# GimbalMotorController2017.net
KiCad netlist of a schematic drawn in EAGLE
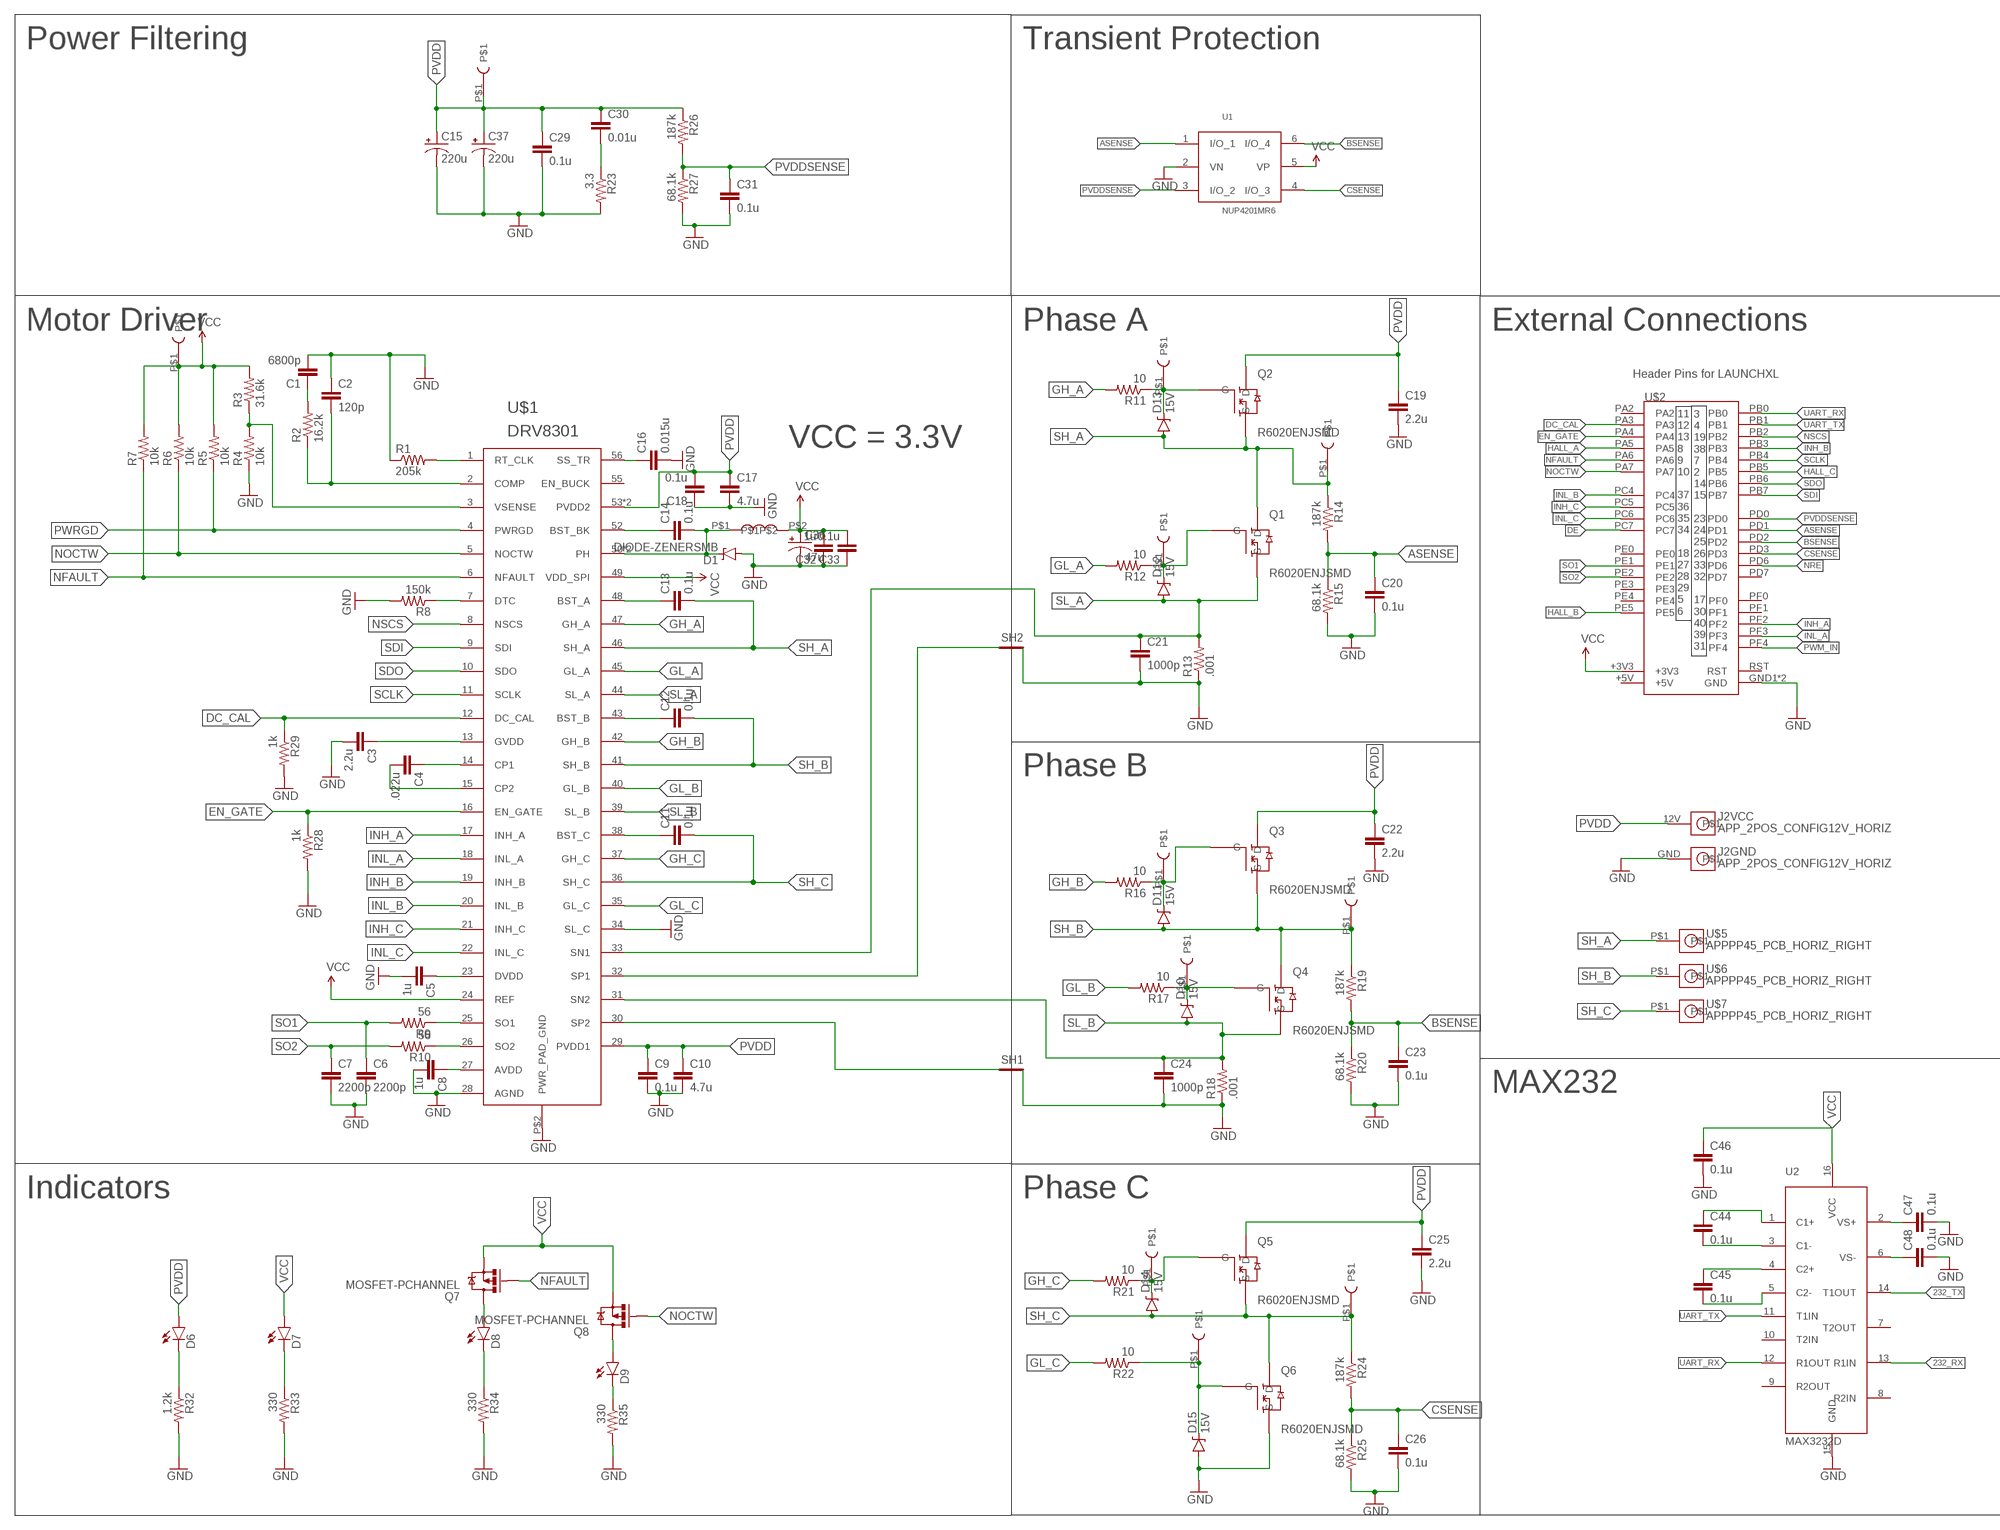
[diagram p0: schematic, sheet 1, part 1 of 2]
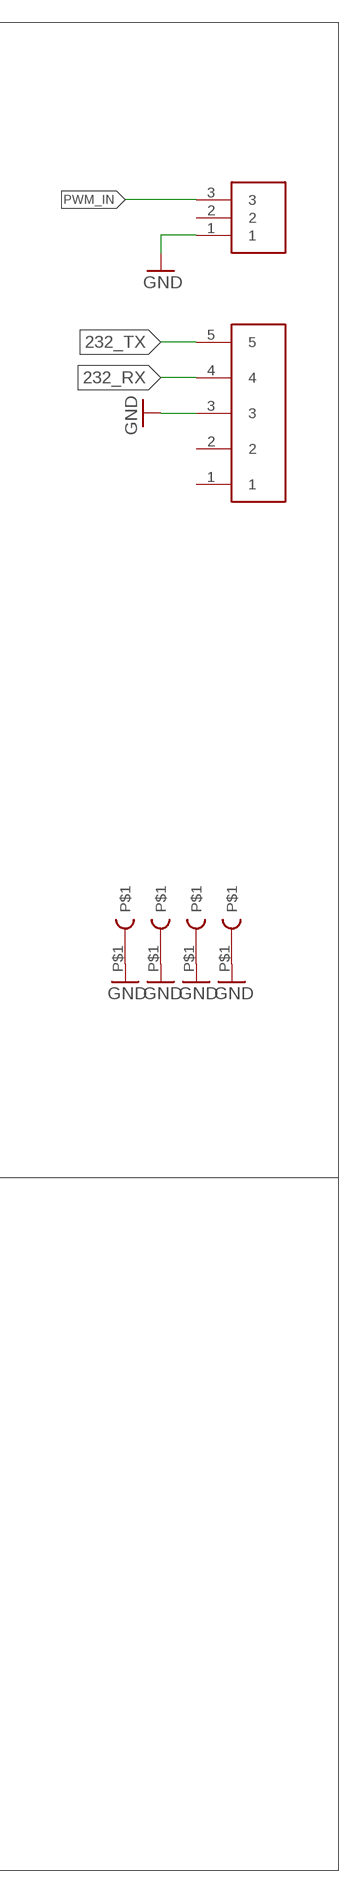
[diagram p1: schematic, sheet 1, part 2 of 2]

(export (version "E")
  (design (tool "Eeschema 10.0.6"))
  (components
    (comp (ref "C1")
      (value "6800p")
      (footprint "eagle-import:0805")
      (libsource (lib "eagle-import") (part "CAP0805"))
    )
    (comp (ref "C2")
      (value "120p")
      (footprint "eagle-import:0805")
      (libsource (lib "eagle-import") (part "CAP0805"))
    )
    (comp (ref "C3")
      (value "2.2u")
      (footprint "eagle-import:1206")
      (libsource (lib "eagle-import") (part "CAP1206"))
    )
    (comp (ref "C4")
      (value ".022u")
      (footprint "eagle-import:0805")
      (libsource (lib "eagle-import") (part "CAP0805"))
    )
    (comp (ref "C5")
      (value "1u")
      (footprint "eagle-import:0805")
      (libsource (lib "eagle-import") (part "CAP0805"))
    )
    (comp (ref "C6")
      (value "2200p")
      (footprint "eagle-import:0805")
      (libsource (lib "eagle-import") (part "CAP0805"))
    )
    (comp (ref "C7")
      (value "2200p")
      (footprint "eagle-import:0805")
      (libsource (lib "eagle-import") (part "CAP0805"))
    )
    (comp (ref "C8")
      (value "1u")
      (footprint "eagle-import:0805")
      (libsource (lib "eagle-import") (part "CAP0805"))
    )
    (comp (ref "C9")
      (value "0.1u")
      (footprint "eagle-import:0805")
      (libsource (lib "eagle-import") (part "CAP0805"))
    )
    (comp (ref "C10")
      (value "4.7u")
      (footprint "eagle-import:1206")
      (libsource (lib "eagle-import") (part "CAP1206"))
    )
    (comp (ref "C11")
      (value "0.1u")
      (footprint "eagle-import:0805")
      (libsource (lib "eagle-import") (part "CAP0805"))
    )
    (comp (ref "C12")
      (value "0.1u")
      (footprint "eagle-import:0805")
      (libsource (lib "eagle-import") (part "CAP0805"))
    )
    (comp (ref "C13")
      (value "0.1u")
      (footprint "eagle-import:0805")
      (libsource (lib "eagle-import") (part "CAP0805"))
    )
    (comp (ref "C14")
      (value "0.1u")
      (footprint "eagle-import:0805")
      (libsource (lib "eagle-import") (part "CAP0805"))
    )
    (comp (ref "C15")
      (value "220u")
      (footprint "eagle-import:CPOL-RADIAL-1000UF-25V")
      (libsource (lib "eagle-import") (part "CAP_POLPTH4"))
    )
    (comp (ref "C16")
      (value "0.015u")
      (footprint "eagle-import:0805")
      (libsource (lib "eagle-import") (part "CAP0805"))
    )
    (comp (ref "C17")
      (value "4.7u")
      (footprint "eagle-import:1206")
      (libsource (lib "eagle-import") (part "CAP1206"))
    )
    (comp (ref "C18")
      (value "0.1u")
      (footprint "eagle-import:0805")
      (libsource (lib "eagle-import") (part "CAP0805"))
    )
    (comp (ref "C19")
      (value "2.2u")
      (footprint "eagle-import:1206")
      (libsource (lib "eagle-import") (part "CAP1206"))
    )
    (comp (ref "C20")
      (value "0.1u")
      (footprint "eagle-import:0805")
      (libsource (lib "eagle-import") (part "CAP0805"))
    )
    (comp (ref "C21")
      (value "1000p")
      (footprint "eagle-import:0805")
      (libsource (lib "eagle-import") (part "CAP0805"))
    )
    (comp (ref "C22")
      (value "2.2u")
      (footprint "eagle-import:1206")
      (libsource (lib "eagle-import") (part "CAP1206"))
    )
    (comp (ref "C23")
      (value "0.1u")
      (footprint "eagle-import:0805")
      (libsource (lib "eagle-import") (part "CAP0805"))
    )
    (comp (ref "C24")
      (value "1000p")
      (footprint "eagle-import:0805")
      (libsource (lib "eagle-import") (part "CAP0805"))
    )
    (comp (ref "C25")
      (value "2.2u")
      (footprint "eagle-import:1206")
      (libsource (lib "eagle-import") (part "CAP1206"))
    )
    (comp (ref "C26")
      (value "0.1u")
      (footprint "eagle-import:0805")
      (libsource (lib "eagle-import") (part "CAP0805"))
    )
    (comp (ref "C29")
      (value "0.1u")
      (footprint "eagle-import:0805")
      (libsource (lib "eagle-import") (part "CAP0805"))
    )
    (comp (ref "C30")
      (value "0.01u")
      (footprint "eagle-import:0805")
      (libsource (lib "eagle-import") (part "CAP0805"))
    )
    (comp (ref "C31")
      (value "0.1u")
      (footprint "eagle-import:0805")
      (libsource (lib "eagle-import") (part "CAP0805"))
    )
    (comp (ref "C32")
      (value "1u")
      (footprint "eagle-import:0805")
      (libsource (lib "eagle-import") (part "CAP0805"))
    )
    (comp (ref "C33")
      (value "0.1u")
      (footprint "eagle-import:0805")
      (libsource (lib "eagle-import") (part "CAP0805"))
    )
    (comp (ref "C36")
      (value "47u")
      (footprint "eagle-import:CPOL-RADIAL-100UF-25V")
      (libsource (lib "eagle-import") (part "CAP_POLPTH1"))
    )
    (comp (ref "C37")
      (value "220u")
      (footprint "eagle-import:CPOL-RADIAL-1000UF-25V")
      (libsource (lib "eagle-import") (part "CAP_POLPTH4"))
    )
    (comp (ref "C44")
      (value "0.1u")
      (footprint "eagle-import:0805")
      (libsource (lib "eagle-import") (part "CAP0805"))
    )
    (comp (ref "C45")
      (value "0.1u")
      (footprint "eagle-import:0805")
      (libsource (lib "eagle-import") (part "CAP0805"))
    )
    (comp (ref "C46")
      (value "0.1u")
      (footprint "eagle-import:0805")
      (libsource (lib "eagle-import") (part "CAP0805"))
    )
    (comp (ref "C47")
      (value "0.1u")
      (footprint "eagle-import:0805")
      (libsource (lib "eagle-import") (part "CAP0805"))
    )
    (comp (ref "C48")
      (value "0.1u")
      (footprint "eagle-import:0805")
      (libsource (lib "eagle-import") (part "CAP0805"))
    )
    (comp (ref "D1")
      (value "DIODE-ZENERSMB")
      (footprint "eagle-import:SMB-DIODE")
      (libsource (lib "eagle-import") (part "DIODE-ZENERSMB"))
    )
    (comp (ref "D6")
      (value "LED1206")
      (footprint "eagle-import:LED-1206")
      (libsource (lib "eagle-import") (part "LED1206"))
    )
    (comp (ref "D7")
      (value "LED1206")
      (footprint "eagle-import:LED-1206")
      (libsource (lib "eagle-import") (part "LED1206"))
    )
    (comp (ref "D8")
      (value "LED1206")
      (footprint "eagle-import:LED-1206")
      (libsource (lib "eagle-import") (part "LED1206"))
    )
    (comp (ref "D9")
      (value "LED1206")
      (footprint "eagle-import:LED-1206")
      (libsource (lib "eagle-import") (part "LED1206"))
    )
    (comp (ref "D10")
      (value "15V")
      (footprint "eagle-import:SOD-323")
      (libsource (lib "eagle-import") (part "DIODE-ZENER3.3V"))
    )
    (comp (ref "D11")
      (value "15V")
      (footprint "eagle-import:SOD-323")
      (libsource (lib "eagle-import") (part "DIODE-ZENER3.3V"))
    )
    (comp (ref "D12")
      (value "15V")
      (footprint "eagle-import:SOD-323")
      (libsource (lib "eagle-import") (part "DIODE-ZENER3.3V"))
    )
    (comp (ref "D13")
      (value "15V")
      (footprint "eagle-import:SOD-323")
      (libsource (lib "eagle-import") (part "DIODE-ZENER3.3V"))
    )
    (comp (ref "D14")
      (value "15V")
      (footprint "eagle-import:SOD-323")
      (libsource (lib "eagle-import") (part "DIODE-ZENER3.3V"))
    )
    (comp (ref "D15")
      (value "15V")
      (footprint "eagle-import:SOD-323")
      (libsource (lib "eagle-import") (part "DIODE-ZENER3.3V"))
    )
    (comp (ref "J1")
      (value "SL03THROUGH_HOLE")
      (footprint "eagle-import:MOLEX_SL_03_TH")
      (fields (field (name "PARTNO") "0705550002"))
      (libsource (lib "eagle-import") (part "SL03THROUGH_HOLE"))
    )
    (comp (ref "J2")
      (value "APP_2POS_CONFIG12V_HORIZ")
      (footprint "eagle-import:APP45_12V_HORIZ_CONFIG")
      (libsource (lib "eagle-import") (part "APP_2POS_CONFIG12V_HORIZ"))
    )
    (comp (ref "Q1")
      (value "R6020ENJSMD")
      (footprint "eagle-import:D2PACK")
      (libsource (lib "eagle-import") (part "R6020ENJSMD"))
    )
    (comp (ref "Q2")
      (value "R6020ENJSMD")
      (footprint "eagle-import:D2PACK")
      (libsource (lib "eagle-import") (part "R6020ENJSMD"))
    )
    (comp (ref "Q3")
      (value "R6020ENJSMD")
      (footprint "eagle-import:D2PACK")
      (libsource (lib "eagle-import") (part "R6020ENJSMD"))
    )
    (comp (ref "Q4")
      (value "R6020ENJSMD")
      (footprint "eagle-import:D2PACK")
      (libsource (lib "eagle-import") (part "R6020ENJSMD"))
    )
    (comp (ref "Q5")
      (value "R6020ENJSMD")
      (footprint "eagle-import:D2PACK")
      (libsource (lib "eagle-import") (part "R6020ENJSMD"))
    )
    (comp (ref "Q6")
      (value "R6020ENJSMD")
      (footprint "eagle-import:D2PACK")
      (libsource (lib "eagle-import") (part "R6020ENJSMD"))
    )
    (comp (ref "Q7")
      (value "MOSFET-PCHANNEL")
      (footprint "eagle-import:SOT23-3")
      (libsource (lib "eagle-import") (part "MOSFET-PCHANNEL"))
    )
    (comp (ref "Q8")
      (value "MOSFET-PCHANNEL")
      (footprint "eagle-import:SOT23-3")
      (libsource (lib "eagle-import") (part "MOSFET-PCHANNEL"))
    )
    (comp (ref "R1")
      (value "205k")
      (footprint "eagle-import:0805")
      (libsource (lib "eagle-import") (part "RESISTOR0805-RES"))
    )
    (comp (ref "R2")
      (value "16.2k")
      (footprint "eagle-import:0805")
      (libsource (lib "eagle-import") (part "RESISTOR0805-RES"))
    )
    (comp (ref "R3")
      (value "31.6k")
      (footprint "eagle-import:0805")
      (libsource (lib "eagle-import") (part "RESISTOR0805-RES"))
    )
    (comp (ref "R4")
      (value "10k")
      (footprint "eagle-import:0805")
      (libsource (lib "eagle-import") (part "RESISTOR0805-RES"))
    )
    (comp (ref "R5")
      (value "10k")
      (footprint "eagle-import:0805")
      (libsource (lib "eagle-import") (part "RESISTOR0805-RES"))
    )
    (comp (ref "R6")
      (value "10k")
      (footprint "eagle-import:0805")
      (libsource (lib "eagle-import") (part "RESISTOR0805-RES"))
    )
    (comp (ref "R7")
      (value "10k")
      (footprint "eagle-import:0805")
      (libsource (lib "eagle-import") (part "RESISTOR0805-RES"))
    )
    (comp (ref "R8")
      (value "150k")
      (footprint "eagle-import:0805")
      (libsource (lib "eagle-import") (part "RESISTOR0805-RES"))
    )
    (comp (ref "R9")
      (value "56")
      (footprint "eagle-import:0805")
      (libsource (lib "eagle-import") (part "RESISTOR0805-RES"))
    )
    (comp (ref "R10")
      (value "56")
      (footprint "eagle-import:0805")
      (libsource (lib "eagle-import") (part "RESISTOR0805-RES"))
    )
    (comp (ref "R11")
      (value "10")
      (footprint "eagle-import:0805")
      (libsource (lib "eagle-import") (part "RESISTOR0805-RES"))
    )
    (comp (ref "R12")
      (value "10")
      (footprint "eagle-import:0805")
      (libsource (lib "eagle-import") (part "RESISTOR0805-RES"))
    )
    (comp (ref "R13")
      (value ".001")
      (footprint "eagle-import:1206")
      (libsource (lib "eagle-import") (part "RESISTOR1206"))
    )
    (comp (ref "R14")
      (value "187k")
      (footprint "eagle-import:0805")
      (libsource (lib "eagle-import") (part "RESISTOR0805-RES"))
    )
    (comp (ref "R15")
      (value "68.1k")
      (footprint "eagle-import:0805")
      (libsource (lib "eagle-import") (part "RESISTOR0805-RES"))
    )
    (comp (ref "R16")
      (value "10")
      (footprint "eagle-import:0805")
      (libsource (lib "eagle-import") (part "RESISTOR0805-RES"))
    )
    (comp (ref "R17")
      (value "10")
      (footprint "eagle-import:0805")
      (libsource (lib "eagle-import") (part "RESISTOR0805-RES"))
    )
    (comp (ref "R18")
      (value ".001")
      (footprint "eagle-import:1206")
      (libsource (lib "eagle-import") (part "RESISTOR1206"))
    )
    (comp (ref "R19")
      (value "187k")
      (footprint "eagle-import:0805")
      (libsource (lib "eagle-import") (part "RESISTOR0805-RES"))
    )
    (comp (ref "R20")
      (value "68.1k")
      (footprint "eagle-import:0805")
      (libsource (lib "eagle-import") (part "RESISTOR0805-RES"))
    )
    (comp (ref "R21")
      (value "10")
      (footprint "eagle-import:0805")
      (libsource (lib "eagle-import") (part "RESISTOR0805-RES"))
    )
    (comp (ref "R22")
      (value "10")
      (footprint "eagle-import:0805")
      (libsource (lib "eagle-import") (part "RESISTOR0805-RES"))
    )
    (comp (ref "R23")
      (value "3.3")
      (footprint "eagle-import:0805")
      (libsource (lib "eagle-import") (part "RESISTOR0805-RES"))
    )
    (comp (ref "R24")
      (value "187k")
      (footprint "eagle-import:0805")
      (libsource (lib "eagle-import") (part "RESISTOR0805-RES"))
    )
    (comp (ref "R25")
      (value "68.1k")
      (footprint "eagle-import:0805")
      (libsource (lib "eagle-import") (part "RESISTOR0805-RES"))
    )
    (comp (ref "R26")
      (value "187k")
      (footprint "eagle-import:0805")
      (libsource (lib "eagle-import") (part "RESISTOR0805-RES"))
    )
    (comp (ref "R27")
      (value "68.1k")
      (footprint "eagle-import:0805")
      (libsource (lib "eagle-import") (part "RESISTOR0805-RES"))
    )
    (comp (ref "R28")
      (value "1k")
      (footprint "eagle-import:0805")
      (libsource (lib "eagle-import") (part "RESISTOR0805-RES"))
    )
    (comp (ref "R29")
      (value "1k")
      (footprint "eagle-import:0805")
      (libsource (lib "eagle-import") (part "RESISTOR0805-RES"))
    )
    (comp (ref "R32")
      (value "1.2k")
      (footprint "eagle-import:0805")
      (libsource (lib "eagle-import") (part "RESISTOR0805-RES"))
    )
    (comp (ref "R33")
      (value "330")
      (footprint "eagle-import:0805")
      (libsource (lib "eagle-import") (part "RESISTOR0805-RES"))
    )
    (comp (ref "R34")
      (value "330")
      (footprint "eagle-import:0805")
      (libsource (lib "eagle-import") (part "RESISTOR0805-RES"))
    )
    (comp (ref "R35")
      (value "330")
      (footprint "eagle-import:0805")
      (libsource (lib "eagle-import") (part "RESISTOR0805-RES"))
    )
    (comp (ref "SH1")
      (value "SHORT-HT5")
      (footprint "eagle-import:SHORT_TOP-50")
      (libsource (lib "eagle-import") (part "SHORT-HT5"))
    )
    (comp (ref "SH2")
      (value "SHORT-HT5")
      (footprint "eagle-import:SHORT_TOP-50")
      (libsource (lib "eagle-import") (part "SHORT-HT5"))
    )
    (comp (ref "U$1")
      (value "DRV8301")
      (footprint "eagle-import:TFSOP-56")
      (libsource (lib "eagle-import") (part "DRV8301"))
    )
    (comp (ref "U$2")
      (value "TIVA-C")
      (footprint "eagle-import:TIVA-C")
      (libsource (lib "eagle-import") (part "TIVA-C"))
    )
    (comp (ref "U$3")
      (value "TEST_POINT_0.1INDIAM")
      (footprint "eagle-import:TEST_POINT_0.1INDIAM")
      (libsource (lib "eagle-import") (part "TEST_POINT_0.1INDIAM"))
    )
    (comp (ref "U$4")
      (value "5PIN")
      (footprint "eagle-import:5PIN")
      (libsource (lib "eagle-import") (part "5PIN"))
    )
    (comp (ref "U$5")
      (value "APPPP45_PCB_HORIZ_RIGHT")
      (footprint "eagle-import:APP45_PCB_HORIZ_RIGHT")
      (libsource (lib "eagle-import") (part "APPPP45_PCB_HORIZ_RIGHT"))
    )
    (comp (ref "U$6")
      (value "APPPP45_PCB_HORIZ_RIGHT")
      (footprint "eagle-import:APP45_PCB_HORIZ_RIGHT")
      (libsource (lib "eagle-import") (part "APPPP45_PCB_HORIZ_RIGHT"))
    )
    (comp (ref "U$7")
      (value "APPPP45_PCB_HORIZ_RIGHT")
      (footprint "eagle-import:APP45_PCB_HORIZ_RIGHT")
      (libsource (lib "eagle-import") (part "APPPP45_PCB_HORIZ_RIGHT"))
    )
    (comp (ref "U$10")
      (value "TEST_POINT_0.1INDIAM")
      (footprint "eagle-import:TEST_POINT_0.1INDIAM")
      (libsource (lib "eagle-import") (part "TEST_POINT_0.1INDIAM"))
    )
    (comp (ref "U$12")
      (value "TEST_POINT_0.1INDIAM")
      (footprint "eagle-import:TEST_POINT_0.1INDIAM")
      (libsource (lib "eagle-import") (part "TEST_POINT_0.1INDIAM"))
    )
    (comp (ref "U$14")
      (value "33u")
      (footprint "eagle-import:INDUCTOR_DR74")
      (libsource (lib "eagle-import") (part "INDUCTOR_DR74"))
    )
    (comp (ref "U$15")
      (value "TEST_POINT_0.1INDIAM")
      (footprint "eagle-import:TEST_POINT_0.1INDIAM")
      (libsource (lib "eagle-import") (part "TEST_POINT_0.1INDIAM"))
    )
    (comp (ref "U$16")
      (value "TEST_POINT_0.1INDIAM")
      (footprint "eagle-import:TEST_POINT_0.1INDIAM")
      (libsource (lib "eagle-import") (part "TEST_POINT_0.1INDIAM"))
    )
    (comp (ref "U$17")
      (value "TEST_POINT_0.1INDIAM")
      (footprint "eagle-import:TEST_POINT_0.1INDIAM")
      (libsource (lib "eagle-import") (part "TEST_POINT_0.1INDIAM"))
    )
    (comp (ref "U$18")
      (value "TEST_POINT_0.1INDIAM")
      (footprint "eagle-import:TEST_POINT_0.1INDIAM")
      (libsource (lib "eagle-import") (part "TEST_POINT_0.1INDIAM"))
    )
    (comp (ref "U$19")
      (value "TEST_POINT_0.1INDIAM")
      (footprint "eagle-import:TEST_POINT_0.1INDIAM")
      (libsource (lib "eagle-import") (part "TEST_POINT_0.1INDIAM"))
    )
    (comp (ref "U$20")
      (value "TEST_POINT_0.1INDIAM")
      (footprint "eagle-import:TEST_POINT_0.1INDIAM")
      (libsource (lib "eagle-import") (part "TEST_POINT_0.1INDIAM"))
    )
    (comp (ref "U$24")
      (value "TEST_POINT_0.1INDIAM")
      (footprint "eagle-import:TEST_POINT_0.1INDIAM")
      (libsource (lib "eagle-import") (part "TEST_POINT_0.1INDIAM"))
    )
    (comp (ref "U$25")
      (value "TEST_POINT_0.1INDIAM")
      (footprint "eagle-import:TEST_POINT_0.1INDIAM")
      (libsource (lib "eagle-import") (part "TEST_POINT_0.1INDIAM"))
    )
    (comp (ref "U$26")
      (value "TEST_POINT_0.1INDIAM")
      (footprint "eagle-import:TEST_POINT_0.1INDIAM")
      (libsource (lib "eagle-import") (part "TEST_POINT_0.1INDIAM"))
    )
    (comp (ref "U$27")
      (value "TEST_POINT_0.1INDIAM")
      (footprint "eagle-import:TEST_POINT_0.1INDIAM")
      (libsource (lib "eagle-import") (part "TEST_POINT_0.1INDIAM"))
    )
    (comp (ref "U$28")
      (value "TEST_POINT_0.1INDIAM")
      (footprint "eagle-import:TEST_POINT_0.1INDIAM")
      (libsource (lib "eagle-import") (part "TEST_POINT_0.1INDIAM"))
    )
    (comp (ref "U$29")
      (value "TEST_POINT_0.1INDIAM")
      (footprint "eagle-import:TEST_POINT_0.1INDIAM")
      (libsource (lib "eagle-import") (part "TEST_POINT_0.1INDIAM"))
    )
    (comp (ref "U1")
      (value "NUP4201MR6")
      (footprint "eagle-import:TSOP-6")
      (libsource (lib "eagle-import") (part "NUP4201MR6"))
    )
    (comp (ref "U2")
      (value "MAX3232D")
      (footprint "eagle-import:SOIC16")
      (libsource (lib "eagle-import") (part "MAX232D3"))
    )
  )
  (nets
    (net (code "1") (name "/+5V") (class "Default")
      (node (ref "U$2") (pin "+5V") (pinfunction "+5V_+5V") (pintype "power_in"))
    )
    (net (code "2") (name "/RST") (class "Default")
      (node (ref "U$2") (pin "RST") (pinfunction "RST_RST") (pintype "power_in"))
    )
    (net (code "3") (name "232_RX") (class "Default")
      (node (ref "U$4") (pin "4") (pinfunction "4_4") (pintype "bidirectional"))
      (node (ref "U2") (pin "13") (pinfunction "R1IN_13") (pintype "bidirectional"))
    )
    (net (code "4") (name "232_TX") (class "Default")
      (node (ref "U$4") (pin "5") (pinfunction "5_5") (pintype "bidirectional"))
      (node (ref "U2") (pin "14") (pinfunction "T1OUT_14") (pintype "bidirectional"))
    )
    (net (code "5") (name "ASENSE") (class "Default")
      (node (ref "C20") (pin "1") (pinfunction "1_1") (pintype "passive"))
      (node (ref "R14") (pin "2") (pinfunction "2_2") (pintype "passive"))
      (node (ref "R15") (pin "1") (pinfunction "1_1") (pintype "passive"))
      (node (ref "U$2") (pin "PD1") (pinfunction "PD1_PD1") (pintype "bidirectional"))
      (node (ref "U1") (pin "1") (pinfunction "I/O_1_1") (pintype "bidirectional"))
    )
    (net (code "6") (name "BSENSE") (class "Default")
      (node (ref "C23") (pin "1") (pinfunction "1_1") (pintype "passive"))
      (node (ref "R19") (pin "2") (pinfunction "2_2") (pintype "passive"))
      (node (ref "R20") (pin "1") (pinfunction "1_1") (pintype "passive"))
      (node (ref "U$2") (pin "PD2") (pinfunction "PD2_PD2") (pintype "bidirectional"))
      (node (ref "U1") (pin "6") (pinfunction "I/O_4_6") (pintype "bidirectional"))
    )
    (net (code "7") (name "CSENSE") (class "Default")
      (node (ref "C26") (pin "1") (pinfunction "1_1") (pintype "passive"))
      (node (ref "R24") (pin "2") (pinfunction "2_2") (pintype "passive"))
      (node (ref "R25") (pin "1") (pinfunction "1_1") (pintype "passive"))
      (node (ref "U$2") (pin "PD3") (pinfunction "PD3_PD3") (pintype "bidirectional"))
      (node (ref "U1") (pin "4") (pinfunction "I/O_3_4") (pintype "bidirectional"))
    )
    (net (code "8") (name "DC_CAL") (class "Default")
      (node (ref "R29") (pin "1") (pinfunction "1_1") (pintype "passive"))
      (node (ref "U$1") (pin "12") (pinfunction "DC_CAL_12") (pintype "bidirectional"))
      (node (ref "U$2") (pin "PA3") (pinfunction "PA3_PA3") (pintype "bidirectional"))
    )
    (net (code "9") (name "DE") (class "Default")
      (node (ref "U$2") (pin "PC7") (pinfunction "PC7_PC7") (pintype "bidirectional"))
    )
    (net (code "10") (name "EN_GATE") (class "Default")
      (node (ref "R28") (pin "1") (pinfunction "1_1") (pintype "passive"))
      (node (ref "U$1") (pin "16") (pinfunction "EN_GATE_16") (pintype "bidirectional"))
      (node (ref "U$2") (pin "PA4") (pinfunction "PA4_PA4") (pintype "bidirectional"))
    )
    (net (code "11") (name "GH_A") (class "Default")
      (node (ref "R11") (pin "2") (pinfunction "2_2") (pintype "passive"))
      (node (ref "U$1") (pin "47") (pinfunction "GH_A_47") (pintype "bidirectional"))
    )
    (net (code "12") (name "GH_B") (class "Default")
      (node (ref "R16") (pin "2") (pinfunction "2_2") (pintype "passive"))
      (node (ref "U$1") (pin "42") (pinfunction "GH_B_42") (pintype "bidirectional"))
    )
    (net (code "13") (name "GH_C") (class "Default")
      (node (ref "R21") (pin "2") (pinfunction "2_2") (pintype "passive"))
      (node (ref "U$1") (pin "37") (pinfunction "GH_C_37") (pintype "bidirectional"))
    )
    (net (code "14") (name "GL_A") (class "Default")
      (node (ref "R12") (pin "2") (pinfunction "2_2") (pintype "passive"))
      (node (ref "U$1") (pin "45") (pinfunction "GL_A_45") (pintype "bidirectional"))
    )
    (net (code "15") (name "GL_B") (class "Default")
      (node (ref "R17") (pin "2") (pinfunction "2_2") (pintype "passive"))
      (node (ref "U$1") (pin "40") (pinfunction "GL_B_40") (pintype "bidirectional"))
    )
    (net (code "16") (name "GL_C") (class "Default")
      (node (ref "R22") (pin "2") (pinfunction "2_2") (pintype "passive"))
      (node (ref "U$1") (pin "35") (pinfunction "GL_C_35") (pintype "bidirectional"))
    )
    (net (code "17") (name "GND") (class "Default")
      (node (ref "C1") (pin "2") (pinfunction "2_2") (pintype "passive"))
      (node (ref "C10") (pin "2") (pinfunction "2_2") (pintype "passive"))
      (node (ref "C15") (pin "2") (pinfunction "-_2") (pintype "passive"))
      (node (ref "C16") (pin "2") (pinfunction "2_2") (pintype "passive"))
      (node (ref "C17") (pin "2") (pinfunction "2_2") (pintype "passive"))
      (node (ref "C18") (pin "1") (pinfunction "1_1") (pintype "passive"))
      (node (ref "C19") (pin "2") (pinfunction "2_2") (pintype "passive"))
      (node (ref "C2") (pin "1") (pinfunction "1_1") (pintype "passive"))
      (node (ref "C20") (pin "2") (pinfunction "2_2") (pintype "passive"))
      (node (ref "C21") (pin "2") (pinfunction "2_2") (pintype "passive"))
      (node (ref "C22") (pin "2") (pinfunction "2_2") (pintype "passive"))
      (node (ref "C23") (pin "2") (pinfunction "2_2") (pintype "passive"))
      (node (ref "C24") (pin "2") (pinfunction "2_2") (pintype "passive"))
      (node (ref "C25") (pin "2") (pinfunction "2_2") (pintype "passive"))
      (node (ref "C26") (pin "2") (pinfunction "2_2") (pintype "passive"))
      (node (ref "C29") (pin "2") (pinfunction "2_2") (pintype "passive"))
      (node (ref "C3") (pin "2") (pinfunction "2_2") (pintype "passive"))
      (node (ref "C31") (pin "2") (pinfunction "2_2") (pintype "passive"))
      (node (ref "C32") (pin "1") (pinfunction "1_1") (pintype "passive"))
      (node (ref "C33") (pin "1") (pinfunction "1_1") (pintype "passive"))
      (node (ref "C36") (pin "2") (pinfunction "-_2") (pintype "passive"))
      (node (ref "C37") (pin "2") (pinfunction "-_2") (pintype "passive"))
      (node (ref "C46") (pin "2") (pinfunction "2_2") (pintype "passive"))
      (node (ref "C47") (pin "2") (pinfunction "2_2") (pintype "passive"))
      (node (ref "C48") (pin "2") (pinfunction "2_2") (pintype "passive"))
      (node (ref "C5") (pin "2") (pinfunction "2_2") (pintype "passive"))
      (node (ref "C6") (pin "2") (pinfunction "2_2") (pintype "passive"))
      (node (ref "C7") (pin "2") (pinfunction "2_2") (pintype "passive"))
      (node (ref "C8") (pin "2") (pinfunction "2_2") (pintype "passive"))
      (node (ref "C9") (pin "2") (pinfunction "2_2") (pintype "passive"))
      (node (ref "D1") (pin "A") (pinfunction "A_A") (pintype "passive"))
      (node (ref "D15") (pin "A") (pinfunction "A_A") (pintype "passive"))
      (node (ref "J1") (pin "1") (pinfunction "1_1") (pintype "bidirectional"))
      (node (ref "J2") (pin "GND") (pinfunction "P$1_GND") (pintype "bidirectional"))
      (node (ref "Q6") (pin "2") (pinfunction "S_2") (pintype "bidirectional"))
      (node (ref "R1") (pin "1") (pinfunction "1_1") (pintype "passive"))
      (node (ref "R13") (pin "1") (pinfunction "1_1") (pintype "passive"))
      (node (ref "R15") (pin "2") (pinfunction "2_2") (pintype "passive"))
      (node (ref "R18") (pin "1") (pinfunction "1_1") (pintype "passive"))
      (node (ref "R20") (pin "2") (pinfunction "2_2") (pintype "passive"))
      (node (ref "R23") (pin "2") (pinfunction "2_2") (pintype "passive"))
      (node (ref "R25") (pin "2") (pinfunction "2_2") (pintype "passive"))
      (node (ref "R27") (pin "2") (pinfunction "2_2") (pintype "passive"))
      (node (ref "R28") (pin "2") (pinfunction "2_2") (pintype "passive"))
      (node (ref "R29") (pin "2") (pinfunction "2_2") (pintype "passive"))
      (node (ref "R32") (pin "2") (pinfunction "2_2") (pintype "passive"))
      (node (ref "R33") (pin "2") (pinfunction "2_2") (pintype "passive"))
      (node (ref "R34") (pin "2") (pinfunction "2_2") (pintype "passive"))
      (node (ref "R35") (pin "2") (pinfunction "2_2") (pintype "passive"))
      (node (ref "R4") (pin "1") (pinfunction "1_1") (pintype "passive"))
      (node (ref "R8") (pin "2") (pinfunction "2_2") (pintype "passive"))
      (node (ref "SH1") (pin "2") (pinfunction "P$2_2") (pintype "bidirectional"))
      (node (ref "SH2") (pin "2") (pinfunction "P$2_2") (pintype "bidirectional"))
      (node (ref "U$1") (pin "28") (pinfunction "AGND_28") (pintype "bidirectional"))
      (node (ref "U$1") (pin "34") (pinfunction "SL_C_34") (pintype "bidirectional"))
      (node (ref "U$1") (pin "P$2") (pinfunction "PWR_PAD_GND_P$2") (pintype "bidirectional"))
      (node (ref "U$2") (pin "GND1") (pinfunction "GND_GND1") (pintype "power_in"))
      (node (ref "U$2") (pin "GND2") (pinfunction "GND_GND2") (pintype "power_in"))
      (node (ref "U$26") (pin "P$1") (pinfunction "P$1_P$1") (pintype "bidirectional"))
      (node (ref "U$27") (pin "P$1") (pinfunction "P$1_P$1") (pintype "bidirectional"))
      (node (ref "U$28") (pin "P$1") (pinfunction "P$1_P$1") (pintype "bidirectional"))
      (node (ref "U$29") (pin "P$1") (pinfunction "P$1_P$1") (pintype "bidirectional"))
      (node (ref "U$4") (pin "3") (pinfunction "3_3") (pintype "bidirectional"))
      (node (ref "U1") (pin "2") (pinfunction "VN_2") (pintype "bidirectional"))
      (node (ref "U2") (pin "15") (pinfunction "GND_15") (pintype "bidirectional"))
    )
    (net (code "18") (name "HALL_A") (class "Default")
      (node (ref "U$2") (pin "PA5") (pinfunction "PA5_PA5") (pintype "bidirectional"))
    )
    (net (code "19") (name "HALL_B") (class "Default")
      (node (ref "U$2") (pin "PE5") (pinfunction "PE5_PE5") (pintype "bidirectional"))
    )
    (net (code "20") (name "HALL_C") (class "Default")
      (node (ref "U$2") (pin "PB5") (pinfunction "PB5_PB5") (pintype "bidirectional"))
    )
    (net (code "21") (name "INH_A") (class "Default")
      (node (ref "U$1") (pin "17") (pinfunction "INH_A_17") (pintype "bidirectional"))
      (node (ref "U$2") (pin "PF2") (pinfunction "PF2_PF2") (pintype "bidirectional"))
    )
    (net (code "22") (name "INH_B") (class "Default")
      (node (ref "U$1") (pin "19") (pinfunction "INH_B_19") (pintype "bidirectional"))
      (node (ref "U$2") (pin "PB3") (pinfunction "PB3_PB3") (pintype "bidirectional"))
    )
    (net (code "23") (name "INH_C") (class "Default")
      (node (ref "U$1") (pin "21") (pinfunction "INH_C_21") (pintype "bidirectional"))
      (node (ref "U$2") (pin "PC5") (pinfunction "PC5_PC5") (pintype "bidirectional"))
    )
    (net (code "24") (name "INL_A") (class "Default")
      (node (ref "U$1") (pin "18") (pinfunction "INL_A_18") (pintype "bidirectional"))
      (node (ref "U$2") (pin "PF3") (pinfunction "PF3_PF3") (pintype "bidirectional"))
    )
    (net (code "25") (name "INL_B") (class "Default")
      (node (ref "U$1") (pin "20") (pinfunction "INL_B_20") (pintype "bidirectional"))
      (node (ref "U$2") (pin "PC4") (pinfunction "PC4_PC4") (pintype "bidirectional"))
    )
    (net (code "26") (name "INL_C") (class "Default")
      (node (ref "U$1") (pin "22") (pinfunction "INL_C_22") (pintype "bidirectional"))
      (node (ref "U$2") (pin "PC6") (pinfunction "PC6_PC6") (pintype "bidirectional"))
    )
    (net (code "27") (name "NFAULT") (class "Default")
      (node (ref "Q7") (pin "1") (pinfunction "G_1") (pintype "passive"))
      (node (ref "R7") (pin "1") (pinfunction "1_1") (pintype "passive"))
      (node (ref "U$1") (pin "6") (pinfunction "NFAULT_6") (pintype "bidirectional"))
      (node (ref "U$2") (pin "PA6") (pinfunction "PA6_PA6") (pintype "bidirectional"))
    )
    (net (code "28") (name "NOCTW") (class "Default")
      (node (ref "Q8") (pin "1") (pinfunction "G_1") (pintype "passive"))
      (node (ref "R6") (pin "1") (pinfunction "1_1") (pintype "passive"))
      (node (ref "U$1") (pin "5") (pinfunction "NOCTW_5") (pintype "bidirectional"))
      (node (ref "U$2") (pin "PA7") (pinfunction "PA7_PA7") (pintype "bidirectional"))
    )
    (net (code "29") (name "NRE") (class "Default")
      (node (ref "U$2") (pin "PD6") (pinfunction "PD6_PD6") (pintype "bidirectional"))
    )
    (net (code "30") (name "NSCS") (class "Default")
      (node (ref "U$1") (pin "8") (pinfunction "NSCS_8") (pintype "bidirectional"))
      (node (ref "U$2") (pin "PB2") (pinfunction "PB2_PB2") (pintype "bidirectional"))
    )
    (net (code "31") (name "Net-(C1-Pad1)") (class "Default")
      (node (ref "C1") (pin "1") (pinfunction "1_1") (pintype "passive"))
      (node (ref "R2") (pin "2") (pinfunction "2_2") (pintype "passive"))
    )
    (net (code "32") (name "Net-(C14-Pad2)") (class "Default")
      (node (ref "C14") (pin "2") (pinfunction "2_2") (pintype "passive"))
      (node (ref "D1") (pin "C") (pinfunction "C_C") (pintype "passive"))
      (node (ref "U$1") (pin "50") (pinfunction "PH_50") (pintype "bidirectional"))
      (node (ref "U$1") (pin "51") (pinfunction "PH_51") (pintype "bidirectional"))
      (node (ref "U$14") (pin "P$1") (pinfunction "P$1_P$1") (pintype "bidirectional"))
    )
    (net (code "33") (name "Net-(C30-Pad2)") (class "Default")
      (node (ref "C30") (pin "2") (pinfunction "2_2") (pintype "passive"))
      (node (ref "R23") (pin "1") (pinfunction "1_1") (pintype "passive"))
    )
    (net (code "34") (name "Net-(D6-PadC)") (class "Default")
      (node (ref "D6") (pin "C") (pinfunction "C_C") (pintype "passive"))
      (node (ref "R32") (pin "1") (pinfunction "1_1") (pintype "passive"))
    )
    (net (code "35") (name "Net-(D7-PadC)") (class "Default")
      (node (ref "D7") (pin "C") (pinfunction "C_C") (pintype "passive"))
      (node (ref "R33") (pin "1") (pinfunction "1_1") (pintype "passive"))
    )
    (net (code "36") (name "Net-(D8-PadC)") (class "Default")
      (node (ref "D8") (pin "C") (pinfunction "C_C") (pintype "passive"))
      (node (ref "R34") (pin "1") (pinfunction "1_1") (pintype "passive"))
    )
    (net (code "37") (name "Net-(D9-PadC)") (class "Default")
      (node (ref "D9") (pin "C") (pinfunction "C_C") (pintype "passive"))
      (node (ref "R35") (pin "1") (pinfunction "1_1") (pintype "passive"))
    )
    (net (code "38") (name "Net-(Q1-G)") (class "Default")
      (node (ref "D12") (pin "C") (pinfunction "C_C") (pintype "passive"))
      (node (ref "Q1") (pin "1") (pinfunction "G_1") (pintype "bidirectional"))
      (node (ref "R12") (pin "1") (pinfunction "1_1") (pintype "passive"))
      (node (ref "U$15") (pin "P$1") (pinfunction "P$1_P$1") (pintype "bidirectional"))
    )
    (net (code "39") (name "Net-(Q2-G)") (class "Default")
      (node (ref "D13") (pin "C") (pinfunction "C_C") (pintype "passive"))
      (node (ref "Q2") (pin "1") (pinfunction "G_1") (pintype "bidirectional"))
      (node (ref "R11") (pin "1") (pinfunction "1_1") (pintype "passive"))
      (node (ref "U$12") (pin "P$1") (pinfunction "P$1_P$1") (pintype "bidirectional"))
    )
    (net (code "40") (name "Net-(Q3-G)") (class "Default")
      (node (ref "D11") (pin "C") (pinfunction "C_C") (pintype "passive"))
      (node (ref "Q3") (pin "1") (pinfunction "G_1") (pintype "bidirectional"))
      (node (ref "R16") (pin "1") (pinfunction "1_1") (pintype "passive"))
      (node (ref "U$16") (pin "P$1") (pinfunction "P$1_P$1") (pintype "bidirectional"))
    )
    (net (code "41") (name "Net-(Q4-G)") (class "Default")
      (node (ref "D10") (pin "C") (pinfunction "C_C") (pintype "passive"))
      (node (ref "Q4") (pin "1") (pinfunction "G_1") (pintype "bidirectional"))
      (node (ref "R17") (pin "1") (pinfunction "1_1") (pintype "passive"))
      (node (ref "U$17") (pin "P$1") (pinfunction "P$1_P$1") (pintype "bidirectional"))
    )
    (net (code "42") (name "Net-(Q5-G)") (class "Default")
      (node (ref "D14") (pin "C") (pinfunction "C_C") (pintype "passive"))
      (node (ref "Q5") (pin "1") (pinfunction "G_1") (pintype "bidirectional"))
      (node (ref "R21") (pin "1") (pinfunction "1_1") (pintype "passive"))
      (node (ref "U$18") (pin "P$1") (pinfunction "P$1_P$1") (pintype "bidirectional"))
    )
    (net (code "43") (name "Net-(Q6-G)") (class "Default")
      (node (ref "D15") (pin "C") (pinfunction "C_C") (pintype "passive"))
      (node (ref "Q6") (pin "1") (pinfunction "G_1") (pintype "bidirectional"))
      (node (ref "R22") (pin "1") (pinfunction "1_1") (pintype "passive"))
      (node (ref "U$19") (pin "P$1") (pinfunction "P$1_P$1") (pintype "bidirectional"))
    )
    (net (code "44") (name "Net-(Q7-D)") (class "Default")
      (node (ref "D8") (pin "A") (pinfunction "A_A") (pintype "passive"))
      (node (ref "Q7") (pin "3") (pinfunction "D_3") (pintype "passive"))
    )
    (net (code "45") (name "Net-(Q8-D)") (class "Default")
      (node (ref "D9") (pin "A") (pinfunction "A_A") (pintype "passive"))
      (node (ref "Q8") (pin "3") (pinfunction "D_3") (pintype "passive"))
    )
    (net (code "46") (name "Net-(SH1-P$1)") (class "Default")
      (node (ref "SH1") (pin "1") (pinfunction "P$1_1") (pintype "bidirectional"))
      (node (ref "U$1") (pin "30") (pinfunction "SP2_30") (pintype "bidirectional"))
    )
    (net (code "47") (name "Net-(SH2-P$1)") (class "Default")
      (node (ref "SH2") (pin "1") (pinfunction "P$1_1") (pintype "bidirectional"))
      (node (ref "U$1") (pin "32") (pinfunction "SP1_32") (pintype "bidirectional"))
    )
    (net (code "48") (name "Net-(U$1-AVDD)") (class "Default")
      (node (ref "C8") (pin "1") (pinfunction "1_1") (pintype "passive"))
      (node (ref "U$1") (pin "27") (pinfunction "AVDD_27") (pintype "bidirectional"))
    )
    (net (code "49") (name "Net-(U$1-BST_A)") (class "Default")
      (node (ref "C13") (pin "1") (pinfunction "1_1") (pintype "passive"))
      (node (ref "U$1") (pin "48") (pinfunction "BST_A_48") (pintype "bidirectional"))
    )
    (net (code "50") (name "Net-(U$1-BST_B)") (class "Default")
      (node (ref "C12") (pin "1") (pinfunction "1_1") (pintype "passive"))
      (node (ref "U$1") (pin "43") (pinfunction "BST_B_43") (pintype "bidirectional"))
    )
    (net (code "51") (name "Net-(U$1-BST_BK)") (class "Default")
      (node (ref "C14") (pin "1") (pinfunction "1_1") (pintype "passive"))
      (node (ref "U$1") (pin "52") (pinfunction "BST_BK_52") (pintype "bidirectional"))
    )
    (net (code "52") (name "Net-(U$1-BST_C)") (class "Default")
      (node (ref "C11") (pin "1") (pinfunction "1_1") (pintype "passive"))
      (node (ref "U$1") (pin "38") (pinfunction "BST_C_38") (pintype "bidirectional"))
    )
    (net (code "53") (name "Net-(U$1-COMP)") (class "Default")
      (node (ref "C2") (pin "2") (pinfunction "2_2") (pintype "passive"))
      (node (ref "R2") (pin "1") (pinfunction "1_1") (pintype "passive"))
      (node (ref "U$1") (pin "2") (pinfunction "COMP_2") (pintype "bidirectional"))
    )
    (net (code "54") (name "Net-(U$1-CP1)") (class "Default")
      (node (ref "C4") (pin "1") (pinfunction "1_1") (pintype "passive"))
      (node (ref "U$1") (pin "14") (pinfunction "CP1_14") (pintype "bidirectional"))
    )
    (net (code "55") (name "Net-(U$1-CP2)") (class "Default")
      (node (ref "C4") (pin "2") (pinfunction "2_2") (pintype "passive"))
      (node (ref "U$1") (pin "15") (pinfunction "CP2_15") (pintype "bidirectional"))
    )
    (net (code "56") (name "Net-(U$1-DTC)") (class "Default")
      (node (ref "R8") (pin "1") (pinfunction "1_1") (pintype "passive"))
      (node (ref "U$1") (pin "7") (pinfunction "DTC_7") (pintype "bidirectional"))
    )
    (net (code "57") (name "Net-(U$1-DVDD)") (class "Default")
      (node (ref "C5") (pin "1") (pinfunction "1_1") (pintype "passive"))
      (node (ref "U$1") (pin "23") (pinfunction "DVDD_23") (pintype "bidirectional"))
    )
    (net (code "58") (name "Net-(U$1-GVDD)") (class "Default")
      (node (ref "C3") (pin "1") (pinfunction "1_1") (pintype "passive"))
      (node (ref "U$1") (pin "13") (pinfunction "GVDD_13") (pintype "bidirectional"))
    )
    (net (code "59") (name "Net-(U$1-RT_CLK)") (class "Default")
      (node (ref "R1") (pin "2") (pinfunction "2_2") (pintype "passive"))
      (node (ref "U$1") (pin "1") (pinfunction "RT_CLK_1") (pintype "bidirectional"))
    )
    (net (code "60") (name "Net-(U$1-SO1)") (class "Default")
      (node (ref "R9") (pin "1") (pinfunction "1_1") (pintype "passive"))
      (node (ref "U$1") (pin "25") (pinfunction "SO1_25") (pintype "bidirectional"))
    )
    (net (code "61") (name "Net-(U$1-SO2)") (class "Default")
      (node (ref "R10") (pin "1") (pinfunction "1_1") (pintype "passive"))
      (node (ref "U$1") (pin "26") (pinfunction "SO2_26") (pintype "bidirectional"))
    )
    (net (code "62") (name "Net-(U$1-SS_TR)") (class "Default")
      (node (ref "C16") (pin "1") (pinfunction "1_1") (pintype "passive"))
      (node (ref "U$1") (pin "56") (pinfunction "SS_TR_56") (pintype "bidirectional"))
    )
    (net (code "63") (name "Net-(U$1-VSENSE)") (class "Default")
      (node (ref "R3") (pin "1") (pinfunction "1_1") (pintype "passive"))
      (node (ref "R4") (pin "2") (pinfunction "2_2") (pintype "passive"))
      (node (ref "U$1") (pin "3") (pinfunction "VSENSE_3") (pintype "bidirectional"))
    )
    (net (code "64") (name "Net-(U2-C1+)") (class "Default")
      (node (ref "C44") (pin "1") (pinfunction "1_1") (pintype "passive"))
      (node (ref "U2") (pin "1") (pinfunction "C1+_1") (pintype "bidirectional"))
    )
    (net (code "65") (name "Net-(U2-C1-)") (class "Default")
      (node (ref "C44") (pin "2") (pinfunction "2_2") (pintype "passive"))
      (node (ref "U2") (pin "3") (pinfunction "C1-_3") (pintype "bidirectional"))
    )
    (net (code "66") (name "Net-(U2-C2+)") (class "Default")
      (node (ref "C45") (pin "1") (pinfunction "1_1") (pintype "passive"))
      (node (ref "U2") (pin "4") (pinfunction "C2+_4") (pintype "bidirectional"))
    )
    (net (code "67") (name "Net-(U2-C2-)") (class "Default")
      (node (ref "C45") (pin "2") (pinfunction "2_2") (pintype "passive"))
      (node (ref "U2") (pin "5") (pinfunction "C2-_5") (pintype "bidirectional"))
    )
    (net (code "68") (name "Net-(U2-VS+)") (class "Default")
      (node (ref "C47") (pin "1") (pinfunction "1_1") (pintype "passive"))
      (node (ref "U2") (pin "2") (pinfunction "VS+_2") (pintype "bidirectional"))
    )
    (net (code "69") (name "Net-(U2-VS-)") (class "Default")
      (node (ref "C48") (pin "1") (pinfunction "1_1") (pintype "passive"))
      (node (ref "U2") (pin "6") (pinfunction "VS-_6") (pintype "bidirectional"))
    )
    (net (code "70") (name "PVDD") (class "Default")
      (node (ref "C10") (pin "1") (pinfunction "1_1") (pintype "passive"))
      (node (ref "C15") (pin "1") (pinfunction "+_1") (pintype "passive"))
      (node (ref "C17") (pin "1") (pinfunction "1_1") (pintype "passive"))
      (node (ref "C18") (pin "2") (pinfunction "2_2") (pintype "passive"))
      (node (ref "C19") (pin "1") (pinfunction "1_1") (pintype "passive"))
      (node (ref "C22") (pin "1") (pinfunction "1_1") (pintype "passive"))
      (node (ref "C25") (pin "1") (pinfunction "1_1") (pintype "passive"))
      (node (ref "C29") (pin "1") (pinfunction "1_1") (pintype "passive"))
      (node (ref "C30") (pin "1") (pinfunction "1_1") (pintype "passive"))
      (node (ref "C37") (pin "1") (pinfunction "+_1") (pintype "passive"))
      (node (ref "C9") (pin "1") (pinfunction "1_1") (pintype "passive"))
      (node (ref "D6") (pin "A") (pinfunction "A_A") (pintype "passive"))
      (node (ref "J2") (pin "12V") (pinfunction "P$1_12V") (pintype "bidirectional"))
      (node (ref "Q2") (pin "TAB") (pinfunction "D_TAB") (pintype "bidirectional"))
      (node (ref "Q3") (pin "TAB") (pinfunction "D_TAB") (pintype "bidirectional"))
      (node (ref "Q5") (pin "TAB") (pinfunction "D_TAB") (pintype "bidirectional"))
      (node (ref "R26") (pin "1") (pinfunction "1_1") (pintype "passive"))
      (node (ref "U$1") (pin "29") (pinfunction "PVDD1_29") (pintype "bidirectional"))
      (node (ref "U$1") (pin "53") (pinfunction "PVDD2_53") (pintype "bidirectional"))
      (node (ref "U$1") (pin "54") (pinfunction "PVDD2_54") (pintype "bidirectional"))
      (node (ref "U$3") (pin "P$1") (pinfunction "P$1_P$1") (pintype "bidirectional"))
    )
    (net (code "71") (name "PVDDSENSE") (class "Default")
      (node (ref "C31") (pin "1") (pinfunction "1_1") (pintype "passive"))
      (node (ref "R26") (pin "2") (pinfunction "2_2") (pintype "passive"))
      (node (ref "R27") (pin "1") (pinfunction "1_1") (pintype "passive"))
      (node (ref "U$2") (pin "PD0") (pinfunction "PD0_PD0") (pintype "bidirectional"))
      (node (ref "U1") (pin "3") (pinfunction "I/O_2_3") (pintype "bidirectional"))
    )
    (net (code "72") (name "PWM_IN") (class "Default")
      (node (ref "J1") (pin "3") (pinfunction "3_3") (pintype "bidirectional"))
      (node (ref "U$2") (pin "PF4") (pinfunction "PF4_PF4") (pintype "bidirectional"))
    )
    (net (code "73") (name "PWRGD") (class "Default")
      (node (ref "R5") (pin "1") (pinfunction "1_1") (pintype "passive"))
      (node (ref "U$1") (pin "4") (pinfunction "PWRGD_4") (pintype "bidirectional"))
    )
    (net (code "74") (name "SCLK") (class "Default")
      (node (ref "U$1") (pin "11") (pinfunction "SCLK_11") (pintype "bidirectional"))
      (node (ref "U$2") (pin "PB4") (pinfunction "PB4_PB4") (pintype "bidirectional"))
    )
    (net (code "75") (name "SDI") (class "Default")
      (node (ref "U$1") (pin "9") (pinfunction "SDI_9") (pintype "bidirectional"))
      (node (ref "U$2") (pin "PB7") (pinfunction "PB7_PB7") (pintype "bidirectional"))
    )
    (net (code "76") (name "SDO") (class "Default")
      (node (ref "U$1") (pin "10") (pinfunction "SDO_10") (pintype "bidirectional"))
      (node (ref "U$2") (pin "PB6") (pinfunction "PB6_PB6") (pintype "bidirectional"))
    )
    (net (code "77") (name "SH_A") (class "Default")
      (node (ref "C13") (pin "2") (pinfunction "2_2") (pintype "passive"))
      (node (ref "D13") (pin "A") (pinfunction "A_A") (pintype "passive"))
      (node (ref "Q1") (pin "TAB") (pinfunction "D_TAB") (pintype "bidirectional"))
      (node (ref "Q2") (pin "2") (pinfunction "S_2") (pintype "bidirectional"))
      (node (ref "R14") (pin "1") (pinfunction "1_1") (pintype "passive"))
      (node (ref "U$1") (pin "46") (pinfunction "SH_A_46") (pintype "bidirectional"))
      (node (ref "U$25") (pin "P$1") (pinfunction "P$1_P$1") (pintype "bidirectional"))
      (node (ref "U$5") (pin "P$1") (pinfunction "P$1_P$1") (pintype "bidirectional"))
    )
    (net (code "78") (name "SH_B") (class "Default")
      (node (ref "C12") (pin "2") (pinfunction "2_2") (pintype "passive"))
      (node (ref "D11") (pin "A") (pinfunction "A_A") (pintype "passive"))
      (node (ref "Q3") (pin "2") (pinfunction "S_2") (pintype "bidirectional"))
      (node (ref "Q4") (pin "TAB") (pinfunction "D_TAB") (pintype "bidirectional"))
      (node (ref "R19") (pin "1") (pinfunction "1_1") (pintype "passive"))
      (node (ref "U$1") (pin "41") (pinfunction "SH_B_41") (pintype "bidirectional"))
      (node (ref "U$24") (pin "P$1") (pinfunction "P$1_P$1") (pintype "bidirectional"))
      (node (ref "U$6") (pin "P$1") (pinfunction "P$1_P$1") (pintype "bidirectional"))
    )
    (net (code "79") (name "SH_C") (class "Default")
      (node (ref "C11") (pin "2") (pinfunction "2_2") (pintype "passive"))
      (node (ref "D14") (pin "A") (pinfunction "A_A") (pintype "passive"))
      (node (ref "Q5") (pin "2") (pinfunction "S_2") (pintype "bidirectional"))
      (node (ref "Q6") (pin "TAB") (pinfunction "D_TAB") (pintype "bidirectional"))
      (node (ref "R24") (pin "1") (pinfunction "1_1") (pintype "passive"))
      (node (ref "U$1") (pin "36") (pinfunction "SH_C_36") (pintype "bidirectional"))
      (node (ref "U$20") (pin "P$1") (pinfunction "P$1_P$1") (pintype "bidirectional"))
      (node (ref "U$7") (pin "P$1") (pinfunction "P$1_P$1") (pintype "bidirectional"))
    )
    (net (code "80") (name "SL_A") (class "Default")
      (node (ref "C21") (pin "1") (pinfunction "1_1") (pintype "passive"))
      (node (ref "D12") (pin "A") (pinfunction "A_A") (pintype "passive"))
      (node (ref "Q1") (pin "2") (pinfunction "S_2") (pintype "bidirectional"))
      (node (ref "R13") (pin "2") (pinfunction "2_2") (pintype "passive"))
      (node (ref "U$1") (pin "33") (pinfunction "SN1_33") (pintype "bidirectional"))
      (node (ref "U$1") (pin "44") (pinfunction "SL_A_44") (pintype "bidirectional"))
    )
    (net (code "81") (name "SL_B") (class "Default")
      (node (ref "C24") (pin "1") (pinfunction "1_1") (pintype "passive"))
      (node (ref "D10") (pin "A") (pinfunction "A_A") (pintype "passive"))
      (node (ref "Q4") (pin "2") (pinfunction "S_2") (pintype "bidirectional"))
      (node (ref "R18") (pin "2") (pinfunction "2_2") (pintype "passive"))
      (node (ref "U$1") (pin "31") (pinfunction "SN2_31") (pintype "bidirectional"))
      (node (ref "U$1") (pin "39") (pinfunction "SL_B_39") (pintype "bidirectional"))
    )
    (net (code "82") (name "SO1") (class "Default")
      (node (ref "C6") (pin "1") (pinfunction "1_1") (pintype "passive"))
      (node (ref "R9") (pin "2") (pinfunction "2_2") (pintype "passive"))
      (node (ref "U$2") (pin "PE1") (pinfunction "PE1_PE1") (pintype "bidirectional"))
    )
    (net (code "83") (name "SO2") (class "Default")
      (node (ref "C7") (pin "1") (pinfunction "1_1") (pintype "passive"))
      (node (ref "R10") (pin "2") (pinfunction "2_2") (pintype "passive"))
      (node (ref "U$2") (pin "PE2") (pinfunction "PE2_PE2") (pintype "bidirectional"))
    )
    (net (code "84") (name "UART_RX") (class "Default")
      (node (ref "U$2") (pin "PB0") (pinfunction "PB0_PB0") (pintype "bidirectional"))
      (node (ref "U2") (pin "12") (pinfunction "R1OUT_12") (pintype "bidirectional"))
    )
    (net (code "85") (name "UART_TX") (class "Default")
      (node (ref "U$2") (pin "PB1") (pinfunction "PB1_PB1") (pintype "bidirectional"))
      (node (ref "U2") (pin "11") (pinfunction "T1IN_11") (pintype "bidirectional"))
    )
    (net (code "86") (name "VCC") (class "Default")
      (node (ref "C32") (pin "2") (pinfunction "2_2") (pintype "passive"))
      (node (ref "C33") (pin "2") (pinfunction "2_2") (pintype "passive"))
      (node (ref "C36") (pin "1") (pinfunction "+_1") (pintype "passive"))
      (node (ref "C46") (pin "1") (pinfunction "1_1") (pintype "passive"))
      (node (ref "D7") (pin "A") (pinfunction "A_A") (pintype "passive"))
      (node (ref "Q7") (pin "2") (pinfunction "S_2") (pintype "passive"))
      (node (ref "Q8") (pin "2") (pinfunction "S_2") (pintype "passive"))
      (node (ref "R3") (pin "2") (pinfunction "2_2") (pintype "passive"))
      (node (ref "R5") (pin "2") (pinfunction "2_2") (pintype "passive"))
      (node (ref "R6") (pin "2") (pinfunction "2_2") (pintype "passive"))
      (node (ref "R7") (pin "2") (pinfunction "2_2") (pintype "passive"))
      (node (ref "U$1") (pin "24") (pinfunction "REF_24") (pintype "bidirectional"))
      (node (ref "U$1") (pin "49") (pinfunction "VDD_SPI_49") (pintype "bidirectional"))
      (node (ref "U$10") (pin "P$1") (pinfunction "P$1_P$1") (pintype "bidirectional"))
      (node (ref "U$14") (pin "P$2") (pinfunction "P$2_P$2") (pintype "bidirectional"))
      (node (ref "U$2") (pin "+3V3") (pinfunction "+3V3_+3V3") (pintype "power_in"))
      (node (ref "U1") (pin "5") (pinfunction "VP_5") (pintype "bidirectional"))
      (node (ref "U2") (pin "16") (pinfunction "VCC_16") (pintype "bidirectional"))
    )
    (net (code "87") (name "unconnected-(J1-Pad2)") (class "Default")
      (node (ref "J1") (pin "2") (pinfunction "2_2") (pintype "bidirectional"))
    )
    (net (code "88") (name "unconnected-(U$1-EN_BUCK-Pad55)") (class "Default")
      (node (ref "U$1") (pin "55") (pinfunction "EN_BUCK_55") (pintype "bidirectional"))
    )
    (net (code "89") (name "unconnected-(U$2-PadPA2)") (class "Default")
      (node (ref "U$2") (pin "PA2") (pinfunction "PA2_PA2") (pintype "bidirectional"))
    )
    (net (code "90") (name "unconnected-(U$2-PadPD7)") (class "Default")
      (node (ref "U$2") (pin "PD7") (pinfunction "PD7_PD7") (pintype "bidirectional"))
    )
    (net (code "91") (name "unconnected-(U$2-PadPE0)") (class "Default")
      (node (ref "U$2") (pin "PE0") (pinfunction "PE0_PE0") (pintype "bidirectional"))
    )
    (net (code "92") (name "unconnected-(U$2-PadPE3)") (class "Default")
      (node (ref "U$2") (pin "PE3") (pinfunction "PE3_PE3") (pintype "bidirectional"))
    )
    (net (code "93") (name "unconnected-(U$2-PadPE4)") (class "Default")
      (node (ref "U$2") (pin "PE4") (pinfunction "PE4_PE4") (pintype "bidirectional"))
    )
    (net (code "94") (name "unconnected-(U$2-PadPF0)") (class "Default")
      (node (ref "U$2") (pin "PF0") (pinfunction "PF0_PF0") (pintype "bidirectional"))
    )
    (net (code "95") (name "unconnected-(U$2-PadPF1)") (class "Default")
      (node (ref "U$2") (pin "PF1") (pinfunction "PF1_PF1") (pintype "bidirectional"))
    )
    (net (code "96") (name "unconnected-(U$4-Pad1)") (class "Default")
      (node (ref "U$4") (pin "1") (pinfunction "1_1") (pintype "bidirectional"))
    )
    (net (code "97") (name "unconnected-(U$4-Pad2)") (class "Default")
      (node (ref "U$4") (pin "2") (pinfunction "2_2") (pintype "bidirectional"))
    )
    (net (code "98") (name "unconnected-(U2-R2IN-Pad8)") (class "Default")
      (node (ref "U2") (pin "8") (pinfunction "R2IN_8") (pintype "bidirectional"))
    )
    (net (code "99") (name "unconnected-(U2-R2OUT-Pad9)") (class "Default")
      (node (ref "U2") (pin "9") (pinfunction "R2OUT_9") (pintype "bidirectional"))
    )
    (net (code "100") (name "unconnected-(U2-T2IN-Pad10)") (class "Default")
      (node (ref "U2") (pin "10") (pinfunction "T2IN_10") (pintype "bidirectional"))
    )
    (net (code "101") (name "unconnected-(U2-T2OUT-Pad7)") (class "Default")
      (node (ref "U2") (pin "7") (pinfunction "T2OUT_7") (pintype "bidirectional"))
    )
  )
)
